# lp_analog_small.net
KiCad netlist of a schematic drawn in EAGLE
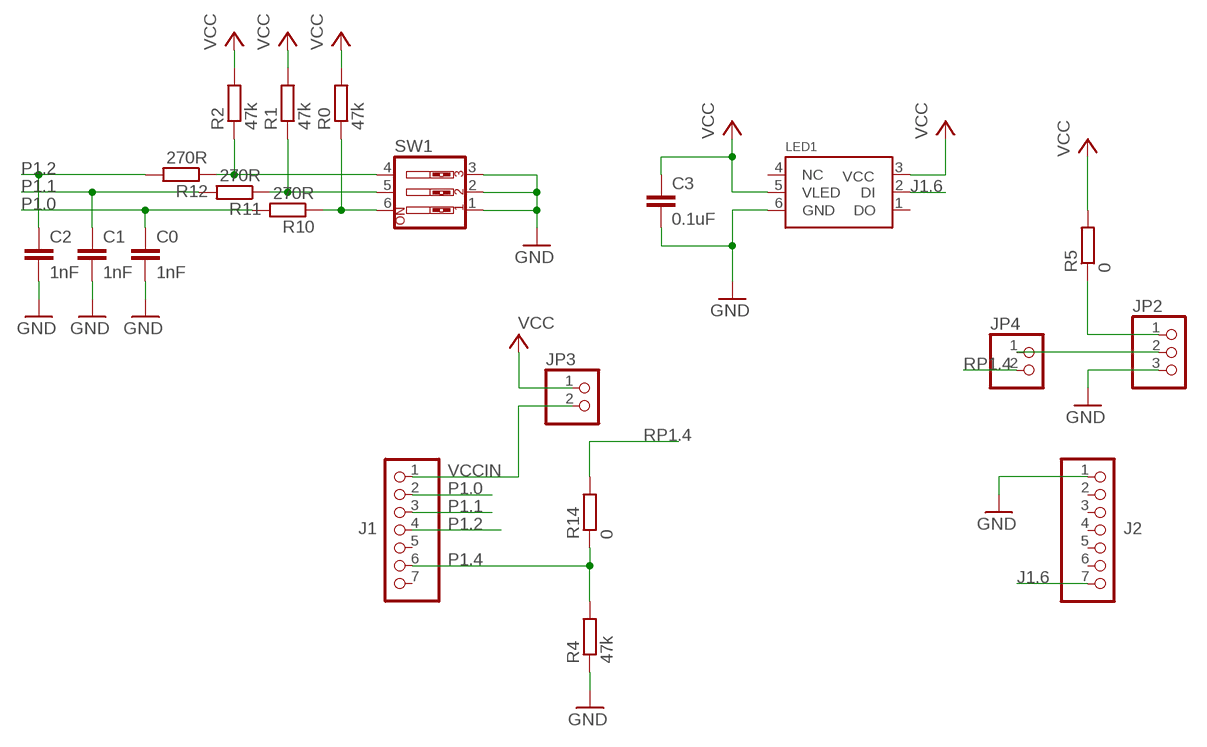
[diagram p0: schematic, sheet 1]

(export (version "E")
  (design (tool "Eeschema 10.0.6"))
  (components
    (comp (ref "C0")
      (value "1nF")
      (footprint "eagle-import:C0805")
      (libsource (lib "eagle-import") (part "resistor_C-EUC0805"))
    )
    (comp (ref "C1")
      (value "1nF")
      (footprint "eagle-import:C0805")
      (libsource (lib "eagle-import") (part "resistor_C-EUC0805"))
    )
    (comp (ref "C2")
      (value "1nF")
      (footprint "eagle-import:C0805")
      (libsource (lib "eagle-import") (part "resistor_C-EUC0805"))
    )
    (comp (ref "C3")
      (value "0.1uF")
      (footprint "eagle-import:C0805")
      (libsource (lib "eagle-import") (part "C-EUC0805"))
    )
    (comp (ref "J1")
      (value "PINHD-1X7")
      (footprint "eagle-import:1X07")
      (libsource (lib "eagle-import") (part "PINHD-1X7"))
    )
    (comp (ref "J2")
      (value "PINHD-1X7")
      (footprint "eagle-import:1X07")
      (libsource (lib "eagle-import") (part "PINHD-1X7"))
    )
    (comp (ref "JP2")
      (value "PINHD-1X3")
      (footprint "eagle-import:1X03")
      (libsource (lib "eagle-import") (part "PINHD-1X3"))
    )
    (comp (ref "JP3")
      (value "PINHD-1X2")
      (footprint "eagle-import:1X02")
      (libsource (lib "eagle-import") (part "PINHD-1X2"))
    )
    (comp (ref "JP4")
      (value "PINHD-1X2")
      (footprint "eagle-import:1X02")
      (libsource (lib "eagle-import") (part "PINHD-1X2"))
    )
    (comp (ref "LED1")
      (value "5050WS2811W")
      (footprint "eagle-import:RGBLED5050W")
      (libsource (lib "eagle-import") (part "5050WS2811W"))
    )
    (comp (ref "R0")
      (value "47k")
      (footprint "eagle-import:R0805")
      (libsource (lib "eagle-import") (part "R-EU_R0805"))
    )
    (comp (ref "R1")
      (value "47k")
      (footprint "eagle-import:R0805")
      (libsource (lib "eagle-import") (part "R-EU_R0805"))
    )
    (comp (ref "R2")
      (value "47k")
      (footprint "eagle-import:R0805")
      (libsource (lib "eagle-import") (part "R-EU_R0805"))
    )
    (comp (ref "R4")
      (value "47k")
      (footprint "eagle-import:R0805")
      (libsource (lib "eagle-import") (part "R-EU_R0805"))
    )
    (comp (ref "R5")
      (value "0")
      (footprint "eagle-import:R0805")
      (libsource (lib "eagle-import") (part "R-EU_R0805"))
    )
    (comp (ref "R10")
      (value "270R")
      (footprint "eagle-import:R0805")
      (libsource (lib "eagle-import") (part "R-EU_R0805"))
    )
    (comp (ref "R11")
      (value "270R")
      (footprint "eagle-import:R0805")
      (libsource (lib "eagle-import") (part "R-EU_R0805"))
    )
    (comp (ref "R12")
      (value "270R")
      (footprint "eagle-import:R0805")
      (libsource (lib "eagle-import") (part "R-EU_R0805"))
    )
    (comp (ref "R14")
      (value "0")
      (footprint "eagle-import:R0805")
      (libsource (lib "eagle-import") (part "R-EU_R0805"))
    )
    (comp (ref "SW1")
      (value "SW_DIP-3")
      (footprint "eagle-import:EDG-03")
      (libsource (lib "eagle-import") (part "SW_DIP-3"))
    )
  )
  (nets
    (net (code "1") (name "/J1.6") (class "Default")
      (node (ref "J2") (pin "7") (pinfunction "7_7") (pintype "passive"))
      (node (ref "LED1") (pin "2") (pinfunction "DI_2") (pintype "bidirectional"))
    )
    (net (code "2") (name "/P1.0") (class "Default")
      (node (ref "C0") (pin "1") (pinfunction "1_1") (pintype "passive"))
      (node (ref "J1") (pin "2") (pinfunction "2_2") (pintype "passive"))
      (node (ref "R10") (pin "2") (pinfunction "2_2") (pintype "passive"))
    )
    (net (code "3") (name "/P1.1") (class "Default")
      (node (ref "C1") (pin "1") (pinfunction "1_1") (pintype "passive"))
      (node (ref "J1") (pin "3") (pinfunction "3_3") (pintype "passive"))
      (node (ref "R11") (pin "2") (pinfunction "2_2") (pintype "passive"))
    )
    (net (code "4") (name "/P1.2") (class "Default")
      (node (ref "C2") (pin "1") (pinfunction "1_1") (pintype "passive"))
      (node (ref "J1") (pin "4") (pinfunction "4_4") (pintype "passive"))
      (node (ref "R12") (pin "2") (pinfunction "2_2") (pintype "passive"))
    )
    (net (code "5") (name "/P1.4") (class "Default")
      (node (ref "J1") (pin "6") (pinfunction "6_6") (pintype "passive"))
      (node (ref "R14") (pin "1") (pinfunction "1_1") (pintype "passive"))
      (node (ref "R4") (pin "2") (pinfunction "2_2") (pintype "passive"))
    )
    (net (code "6") (name "/RP1.4") (class "Default")
      (node (ref "JP4") (pin "2") (pinfunction "2_2") (pintype "passive"))
      (node (ref "R14") (pin "2") (pinfunction "2_2") (pintype "passive"))
    )
    (net (code "7") (name "/VCCIN") (class "Default")
      (node (ref "J1") (pin "1") (pinfunction "1_1") (pintype "passive"))
      (node (ref "JP3") (pin "2") (pinfunction "2_2") (pintype "passive"))
    )
    (net (code "8") (name "GND") (class "Default")
      (node (ref "C0") (pin "2") (pinfunction "2_2") (pintype "passive"))
      (node (ref "C1") (pin "2") (pinfunction "2_2") (pintype "passive"))
      (node (ref "C2") (pin "2") (pinfunction "2_2") (pintype "passive"))
      (node (ref "C3") (pin "2") (pinfunction "2_2") (pintype "passive"))
      (node (ref "J2") (pin "1") (pinfunction "1_1") (pintype "passive"))
      (node (ref "JP2") (pin "3") (pinfunction "3_3") (pintype "passive"))
      (node (ref "LED1") (pin "6") (pinfunction "GND_6") (pintype "bidirectional"))
      (node (ref "R4") (pin "1") (pinfunction "1_1") (pintype "passive"))
      (node (ref "SW1") (pin "1") (pinfunction "1_1") (pintype "passive"))
      (node (ref "SW1") (pin "2") (pinfunction "2_2") (pintype "passive"))
      (node (ref "SW1") (pin "3") (pinfunction "3_3") (pintype "passive"))
    )
    (net (code "9") (name "Net-(JP2-Pad1)") (class "Default")
      (node (ref "JP2") (pin "1") (pinfunction "1_1") (pintype "passive"))
      (node (ref "R5") (pin "1") (pinfunction "1_1") (pintype "passive"))
    )
    (net (code "10") (name "Net-(JP2-Pad2)") (class "Default")
      (node (ref "JP2") (pin "2") (pinfunction "2_2") (pintype "passive"))
      (node (ref "JP4") (pin "1") (pinfunction "1_1") (pintype "passive"))
    )
    (net (code "11") (name "Net-(R0-Pad1)") (class "Default")
      (node (ref "R0") (pin "1") (pinfunction "1_1") (pintype "passive"))
      (node (ref "R10") (pin "1") (pinfunction "1_1") (pintype "passive"))
      (node (ref "SW1") (pin "6") (pinfunction "6_6") (pintype "passive"))
    )
    (net (code "12") (name "Net-(R1-Pad1)") (class "Default")
      (node (ref "R1") (pin "1") (pinfunction "1_1") (pintype "passive"))
      (node (ref "R11") (pin "1") (pinfunction "1_1") (pintype "passive"))
      (node (ref "SW1") (pin "5") (pinfunction "5_5") (pintype "passive"))
    )
    (net (code "13") (name "Net-(R12-Pad1)") (class "Default")
      (node (ref "R12") (pin "1") (pinfunction "1_1") (pintype "passive"))
      (node (ref "R2") (pin "1") (pinfunction "1_1") (pintype "passive"))
      (node (ref "SW1") (pin "4") (pinfunction "4_4") (pintype "passive"))
    )
    (net (code "14") (name "VCC") (class "Default")
      (node (ref "C3") (pin "1") (pinfunction "1_1") (pintype "passive"))
      (node (ref "JP3") (pin "1") (pinfunction "1_1") (pintype "passive"))
      (node (ref "LED1") (pin "3") (pinfunction "VCC_3") (pintype "bidirectional"))
      (node (ref "LED1") (pin "5") (pinfunction "VLED_5") (pintype "bidirectional"))
      (node (ref "R0") (pin "2") (pinfunction "2_2") (pintype "passive"))
      (node (ref "R1") (pin "2") (pinfunction "2_2") (pintype "passive"))
      (node (ref "R2") (pin "2") (pinfunction "2_2") (pintype "passive"))
      (node (ref "R5") (pin "2") (pinfunction "2_2") (pintype "passive"))
    )
    (net (code "15") (name "unconnected-(J1-Pad5)") (class "Default")
      (node (ref "J1") (pin "5") (pinfunction "5_5") (pintype "passive"))
    )
    (net (code "16") (name "unconnected-(J1-Pad7)") (class "Default")
      (node (ref "J1") (pin "7") (pinfunction "7_7") (pintype "passive"))
    )
    (net (code "17") (name "unconnected-(J2-Pad2)") (class "Default")
      (node (ref "J2") (pin "2") (pinfunction "2_2") (pintype "passive"))
    )
    (net (code "18") (name "unconnected-(J2-Pad3)") (class "Default")
      (node (ref "J2") (pin "3") (pinfunction "3_3") (pintype "passive"))
    )
    (net (code "19") (name "unconnected-(J2-Pad4)") (class "Default")
      (node (ref "J2") (pin "4") (pinfunction "4_4") (pintype "passive"))
    )
    (net (code "20") (name "unconnected-(J2-Pad5)") (class "Default")
      (node (ref "J2") (pin "5") (pinfunction "5_5") (pintype "passive"))
    )
    (net (code "21") (name "unconnected-(J2-Pad6)") (class "Default")
      (node (ref "J2") (pin "6") (pinfunction "6_6") (pintype "passive"))
    )
    (net (code "22") (name "unconnected-(LED1-DO-Pad1)") (class "Default")
      (node (ref "LED1") (pin "1") (pinfunction "DO_1") (pintype "bidirectional"))
    )
    (net (code "23") (name "unconnected-(LED1-NC-Pad4)") (class "Default")
      (node (ref "LED1") (pin "4") (pinfunction "NC_4") (pintype "bidirectional"))
    )
  )
)
